# RS232_IrDA.net
KiCad netlist of a schematic drawn in Altium Designer
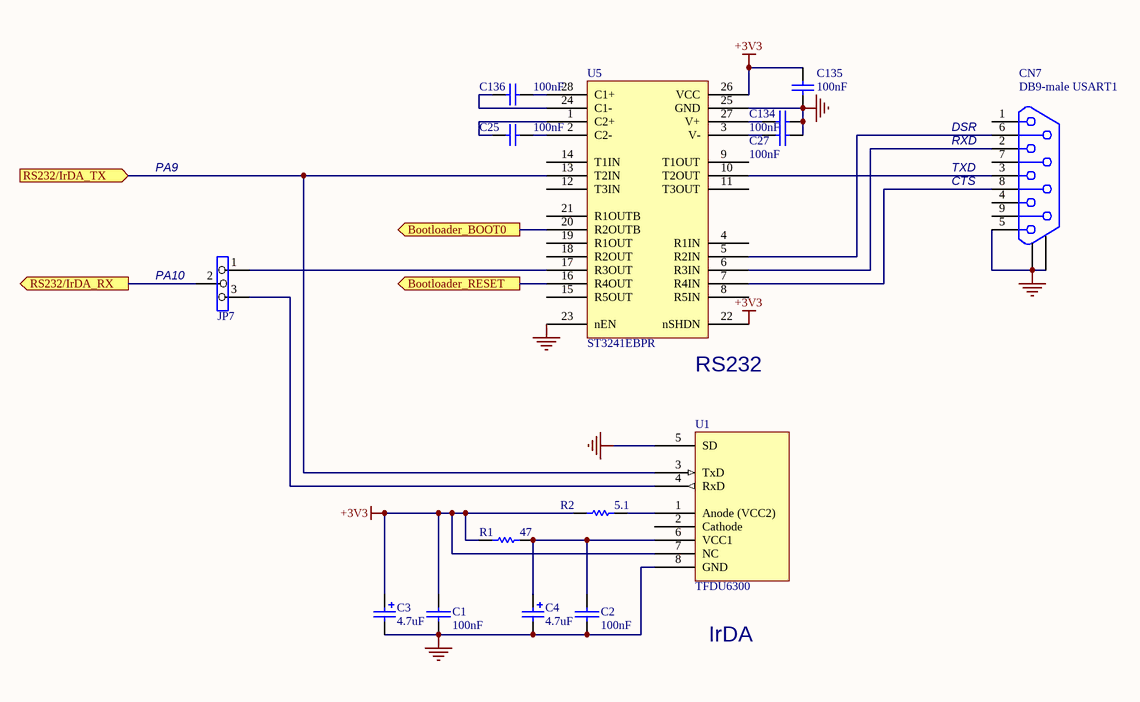
[diagram p0: RS232&IrDA.SchDoc]

(export (version "E")
  (design (tool "Eeschema 10.0.6"))
  (components
    (comp (ref "C1")
      (value "100nF")
      (footprint "0603C")
      (description "Capacitor")
      (libsource (lib "*") (part "CAP"))
    )
    (comp (ref "C2")
      (value "100nF")
      (footprint "0603C")
      (description "Capacitor")
      (libsource (lib "*") (part "CAP"))
    )
    (comp (ref "C3")
      (value "4.7uF")
      (footprint "TAN-A")
      (description "Polarized Capacitor (Radial)")
      (fields (field (name "PUBLISHER") "Altium Limited"))
      (libsource (lib "Miscellaneous Devices") (part "Cap Pol1"))
    )
    (comp (ref "C4")
      (value "4.7uF")
      (footprint "TAN-A")
      (description "Polarized Capacitor (Radial)")
      (fields (field (name "PUBLISHER") "Altium Limited"))
      (libsource (lib "Miscellaneous Devices") (part "Cap Pol1"))
    )
    (comp (ref "C25")
      (value "100nF")
      (footprint "0603C")
      (description "Capacitor")
      (fields (field (name "PUBLISHER") "Altium Limited"))
      (libsource (lib "Miscellaneous Devices") (part "Cap"))
    )
    (comp (ref "C27")
      (value "100nF")
      (footprint "0603C")
      (description "Capacitor")
      (fields (field (name "PUBLISHER") "Altium Limited"))
      (libsource (lib "Miscellaneous Devices") (part "Cap"))
    )
    (comp (ref "C134")
      (value "100nF")
      (footprint "0603C")
      (description "Capacitor")
      (fields (field (name "PUBLISHER") "Altium Limited"))
      (libsource (lib "Miscellaneous Devices") (part "Cap"))
    )
    (comp (ref "C135")
      (value "100nF")
      (footprint "0603C")
      (description "Capacitor")
      (fields (field (name "PUBLISHER") "Altium Limited"))
      (libsource (lib "Miscellaneous Devices") (part "Cap"))
    )
    (comp (ref "C136")
      (value "100nF")
      (footprint "0603C")
      (description "Capacitor")
      (fields (field (name "PUBLISHER") "Altium Limited"))
      (libsource (lib "Miscellaneous Devices") (part "Cap"))
    )
    (comp (ref "CN7")
      (value "DB9-male USART1")
      (footprint "DB9/M")
      (libsource (lib "mb1045") (part "DB9-USART"))
    )
    (comp (ref "JP7") (value "~") (footprint "SIP3") (libsource (lib "STR910_SCHLIB") (part "Jumper3")))
    (comp (ref "R1")
      (value "47")
      (footprint "0603R")
      (description "Resistor")
      (fields (field (name "PUBLISHER") "Altium Limited"))
      (libsource (lib "Miscellaneous Devices") (part "Res1"))
    )
    (comp (ref "R2")
      (value "5.1")
      (footprint "0603R")
      (description "Resistor")
      (fields (field (name "PUBLISHER") "Altium Limited"))
      (libsource (lib "Miscellaneous Devices") (part "Res1"))
    )
    (comp (ref "U1")
      (value "TFDU6300")
      (footprint "IR_VISHAY3")
      (description "TFDU4300")
      (libsource (lib "*") (part "TFDU4300"))
    )
    (comp (ref "U5")
      (value "ST3241EBPR")
      (footprint "SSOP28_0R65_10R2X7R8")
      (libsource (lib "*") (part "ST3241"))
    )
  )
  (nets
    (net (code "1") (name "+3V3") (class "Default")
      (node (ref "C1") (pin "1") (pinfunction "1_1") (pintype "passive"))
      (node (ref "C135") (pin "1") (pinfunction "1_1") (pintype "passive"))
      (node (ref "C3") (pin "1") (pinfunction "1_1") (pintype "passive"))
      (node (ref "R1") (pin "1") (pinfunction "1_1") (pintype "passive"))
      (node (ref "R2") (pin "1") (pinfunction "1_1") (pintype "passive"))
      (node (ref "U1") (pin "7") (pinfunction "NC_7") (pintype "passive"))
      (node (ref "U5") (pin "22") (pinfunction "nSHDN_22") (pintype "passive"))
      (node (ref "U5") (pin "26") (pinfunction "VCC_26") (pintype "passive"))
    )
    (net (code "2") (name "/Bootloader_BOOT0") (class "Default")
      (node (ref "U5") (pin "20") (pinfunction "R2OUTB_20") (pintype "passive"))
    )
    (net (code "3") (name "/Bootloader_RESET") (class "Default")
      (node (ref "U5") (pin "16") (pinfunction "R4OUT_16") (pintype "passive"))
    )
    (net (code "4") (name "/RS232{slash}IrDA_RX") (class "Default")
      (node (ref "JP7") (pin "2") (pintype "passive"))
    )
    (net (code "5") (name "/RS232{slash}IrDA_TX") (class "Default")
      (node (ref "U1") (pin "3") (pinfunction "TxD_3") (pintype "input"))
      (node (ref "U5") (pin "13") (pinfunction "T2IN_13") (pintype "passive"))
    )
    (net (code "6") (name "GND") (class "Default")
      (node (ref "C1") (pin "2") (pinfunction "2_2") (pintype "passive"))
      (node (ref "C134") (pin "1") (pinfunction "1_1") (pintype "passive"))
      (node (ref "C135") (pin "2") (pinfunction "2_2") (pintype "passive"))
      (node (ref "C2") (pin "2") (pinfunction "2_2") (pintype "passive"))
      (node (ref "C27") (pin "1") (pinfunction "1_1") (pintype "passive"))
      (node (ref "C3") (pin "2") (pinfunction "2_2") (pintype "passive"))
      (node (ref "C4") (pin "2") (pinfunction "2_2") (pintype "passive"))
      (node (ref "CN7") (pin "10") (pinfunction "10_10") (pintype "passive"))
      (node (ref "CN7") (pin "11") (pinfunction "11_11") (pintype "passive"))
      (node (ref "CN7") (pin "5") (pinfunction "5_5") (pintype "passive"))
      (node (ref "U1") (pin "5") (pinfunction "SD_5") (pintype "passive"))
      (node (ref "U1") (pin "8") (pinfunction "GND_8") (pintype "passive"))
      (node (ref "U5") (pin "23") (pinfunction "nEN_23") (pintype "passive"))
      (node (ref "U5") (pin "25") (pinfunction "GND_25") (pintype "passive"))
    )
    (net (code "7") (name "Net-(U1-Anode_(VCC2))") (class "Default")
      (node (ref "R2") (pin "2") (pinfunction "2_2") (pintype "passive"))
      (node (ref "U1") (pin "1") (pinfunction "Anode_(VCC2)_1") (pintype "passive"))
    )
    (net (code "8") (name "Net-(U1-RxD)") (class "Default")
      (node (ref "JP7") (pin "3") (pintype "passive"))
      (node (ref "U1") (pin "4") (pinfunction "RxD_4") (pintype "output"))
    )
    (net (code "9") (name "Net-(U1-VCC1)") (class "Default")
      (node (ref "C2") (pin "1") (pinfunction "1_1") (pintype "passive"))
      (node (ref "C4") (pin "1") (pinfunction "1_1") (pintype "passive"))
      (node (ref "R1") (pin "2") (pinfunction "2_2") (pintype "passive"))
      (node (ref "U1") (pin "6") (pinfunction "VCC1_6") (pintype "passive"))
    )
    (net (code "10") (name "Net-(U5-C1+)") (class "Default")
      (node (ref "C136") (pin "2") (pinfunction "2_2") (pintype "passive"))
      (node (ref "U5") (pin "28") (pinfunction "C1+_28") (pintype "passive"))
    )
    (net (code "11") (name "Net-(U5-C1-)") (class "Default")
      (node (ref "C136") (pin "1") (pinfunction "1_1") (pintype "passive"))
      (node (ref "U5") (pin "24") (pinfunction "C1-_24") (pintype "passive"))
    )
    (net (code "12") (name "Net-(U5-C2+)") (class "Default")
      (node (ref "C25") (pin "1") (pinfunction "1_1") (pintype "passive"))
      (node (ref "U5") (pin "1") (pinfunction "C2+_1") (pintype "passive"))
    )
    (net (code "13") (name "Net-(U5-C2-)") (class "Default")
      (node (ref "C25") (pin "2") (pinfunction "2_2") (pintype "passive"))
      (node (ref "U5") (pin "2") (pinfunction "C2-_2") (pintype "passive"))
    )
    (net (code "14") (name "Net-(U5-R2IN)") (class "Default")
      (node (ref "CN7") (pin "6") (pinfunction "6_6") (pintype "passive"))
      (node (ref "U5") (pin "5") (pinfunction "R2IN_5") (pintype "passive"))
    )
    (net (code "15") (name "Net-(U5-R3IN)") (class "Default")
      (node (ref "CN7") (pin "2") (pinfunction "2_2") (pintype "passive"))
      (node (ref "U5") (pin "6") (pinfunction "R3IN_6") (pintype "passive"))
    )
    (net (code "16") (name "Net-(U5-R3OUT)") (class "Default")
      (node (ref "JP7") (pin "1") (pintype "passive"))
      (node (ref "U5") (pin "17") (pinfunction "R3OUT_17") (pintype "passive"))
    )
    (net (code "17") (name "Net-(U5-R4IN)") (class "Default")
      (node (ref "CN7") (pin "8") (pinfunction "8_8") (pintype "passive"))
      (node (ref "U5") (pin "7") (pinfunction "R4IN_7") (pintype "passive"))
    )
    (net (code "18") (name "Net-(U5-T2OUT)") (class "Default")
      (node (ref "CN7") (pin "3") (pinfunction "3_3") (pintype "passive"))
      (node (ref "U5") (pin "10") (pinfunction "T2OUT_10") (pintype "passive"))
    )
    (net (code "19") (name "Net-(U5-V+)") (class "Default")
      (node (ref "C134") (pin "2") (pinfunction "2_2") (pintype "passive"))
      (node (ref "U5") (pin "27") (pinfunction "V+_27") (pintype "passive"))
    )
    (net (code "20") (name "Net-(U5-V-)") (class "Default")
      (node (ref "C27") (pin "2") (pinfunction "2_2") (pintype "passive"))
      (node (ref "U5") (pin "3") (pinfunction "V-_3") (pintype "passive"))
    )
    (net (code "21") (name "unconnected-(CN7-Pad1)") (class "Default")
      (node (ref "CN7") (pin "1") (pinfunction "1_1") (pintype "passive"))
    )
    (net (code "22") (name "unconnected-(CN7-Pad4)") (class "Default")
      (node (ref "CN7") (pin "4") (pinfunction "4_4") (pintype "passive"))
    )
    (net (code "23") (name "unconnected-(CN7-Pad7)") (class "Default")
      (node (ref "CN7") (pin "7") (pinfunction "7_7") (pintype "passive"))
    )
    (net (code "24") (name "unconnected-(CN7-Pad9)") (class "Default")
      (node (ref "CN7") (pin "9") (pinfunction "9_9") (pintype "passive"))
    )
    (net (code "25") (name "unconnected-(U1-Cathode-Pad2)") (class "Default")
      (node (ref "U1") (pin "2") (pinfunction "Cathode_2") (pintype "passive"))
    )
    (net (code "26") (name "unconnected-(U5-R1IN-Pad4)") (class "Default")
      (node (ref "U5") (pin "4") (pinfunction "R1IN_4") (pintype "passive"))
    )
    (net (code "27") (name "unconnected-(U5-R1OUT-Pad19)") (class "Default")
      (node (ref "U5") (pin "19") (pinfunction "R1OUT_19") (pintype "passive"))
    )
    (net (code "28") (name "unconnected-(U5-R1OUTB-Pad21)") (class "Default")
      (node (ref "U5") (pin "21") (pinfunction "R1OUTB_21") (pintype "passive"))
    )
    (net (code "29") (name "unconnected-(U5-R2OUT-Pad18)") (class "Default")
      (node (ref "U5") (pin "18") (pinfunction "R2OUT_18") (pintype "passive"))
    )
    (net (code "30") (name "unconnected-(U5-R5IN-Pad8)") (class "Default")
      (node (ref "U5") (pin "8") (pinfunction "R5IN_8") (pintype "passive"))
    )
    (net (code "31") (name "unconnected-(U5-R5OUT-Pad15)") (class "Default")
      (node (ref "U5") (pin "15") (pinfunction "R5OUT_15") (pintype "passive"))
    )
    (net (code "32") (name "unconnected-(U5-T1IN-Pad14)") (class "Default")
      (node (ref "U5") (pin "14") (pinfunction "T1IN_14") (pintype "passive"))
    )
    (net (code "33") (name "unconnected-(U5-T1OUT-Pad9)") (class "Default")
      (node (ref "U5") (pin "9") (pinfunction "T1OUT_9") (pintype "passive"))
    )
    (net (code "34") (name "unconnected-(U5-T3IN-Pad12)") (class "Default")
      (node (ref "U5") (pin "12") (pinfunction "T3IN_12") (pintype "passive"))
    )
    (net (code "35") (name "unconnected-(U5-T3OUT-Pad11)") (class "Default")
      (node (ref "U5") (pin "11") (pinfunction "T3OUT_11") (pintype "passive"))
    )
  )
)
